# TOP.net
KiCad netlist of a schematic drawn in Altium Designer
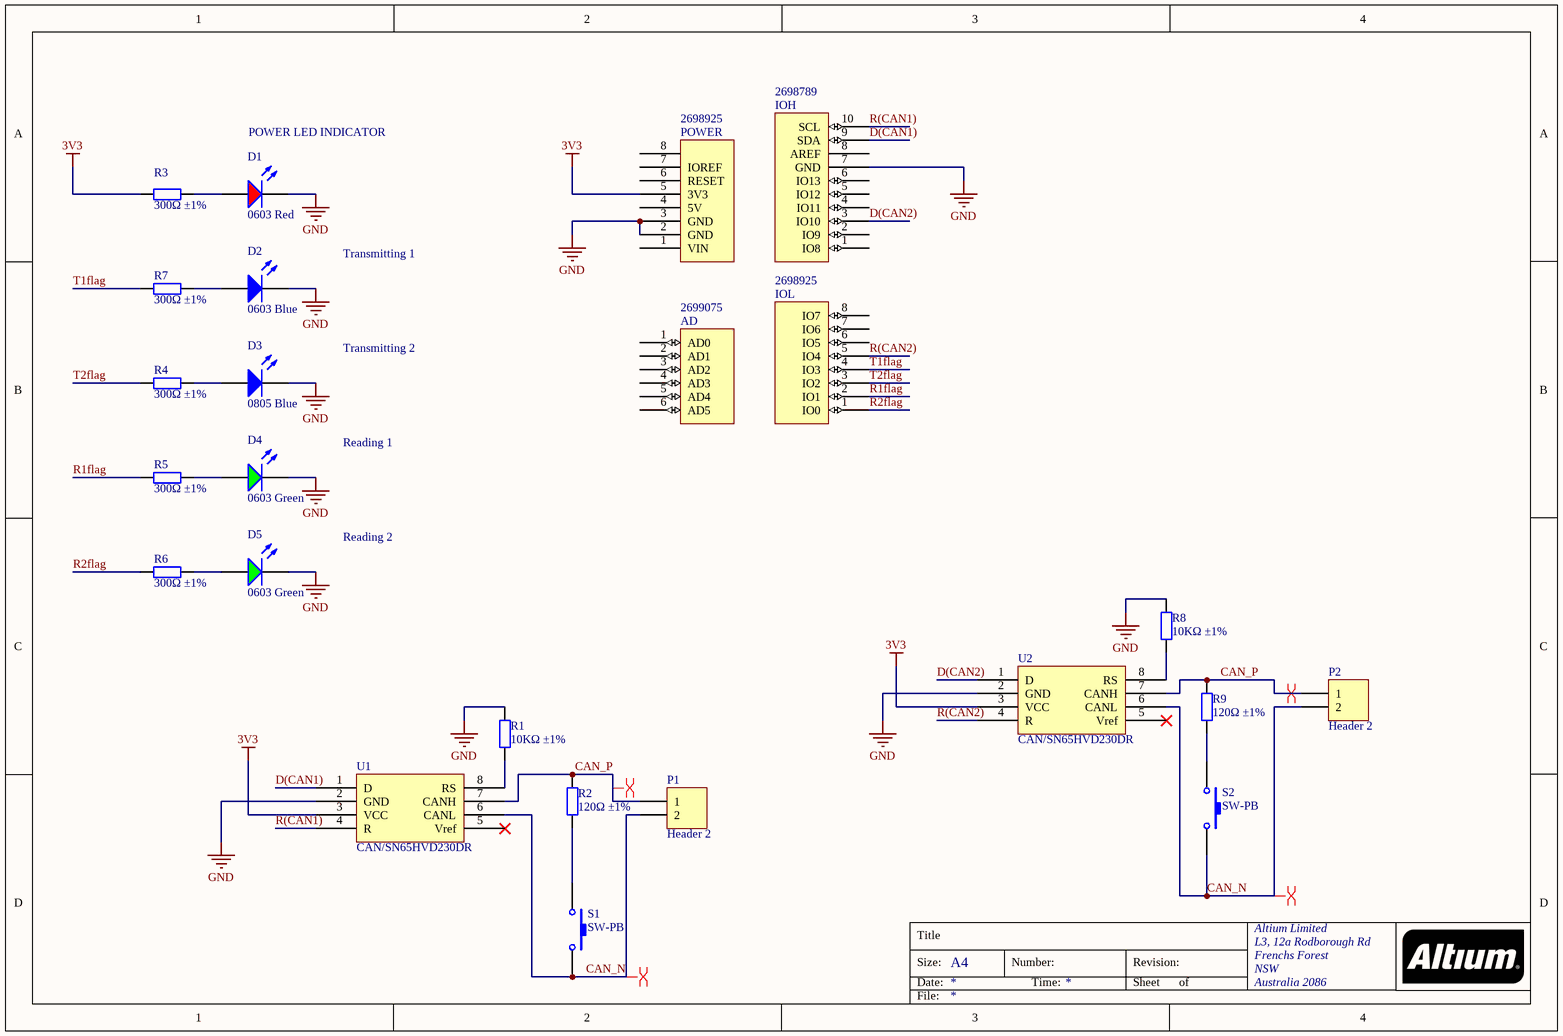
[diagram p0: TOP.SchDoc]

(export (version "E")
  (design (tool "Eeschema 10.0.6"))
  (components
    (comp (ref "AD")
      (value "AD")
      (footprint "Header:Header 6x1 8.5mm")
      (fields (field (name "SUPPLIER PART NUMBER 4") "2699075"))
      (libsource (lib "Header") (part "AD"))
    )
    (comp (ref "D1")
      (value "0603 Red")
      (footprint "0603_LED_S1")
      (description "LED")
      (libsource (lib "LED") (part "0603 LED Red"))
    )
    (comp (ref "D2")
      (value "0603 Blue")
      (footprint "0603_LED_S1")
      (description "LED")
      (libsource (lib "LED") (part "0603 LED Blue"))
    )
    (comp (ref "D3")
      (value "0805 Blue")
      (footprint "0805_LED_S1")
      (description "LED")
      (libsource (lib "LED") (part "0805 LED Blue"))
    )
    (comp (ref "D4")
      (value "0603 Green")
      (footprint "0603_LED_S1")
      (description "LED")
      (libsource (lib "LED") (part "0603 LED Green"))
    )
    (comp (ref "D5")
      (value "0603 Green")
      (footprint "0603_LED_S1")
      (description "LED")
      (libsource (lib "LED") (part "0603 LED Green"))
    )
    (comp (ref "IOH")
      (value "IOH")
      (footprint "Header:Header 10x1 8.5mm")
      (fields (field (name "SUPPLIER PART NUMBER 3") "2698789"))
      (libsource (lib "Header") (part "IOH"))
    )
    (comp (ref "IOL")
      (value "IOL")
      (footprint "Header 8x1 8.5mm")
      (fields (field (name "SUPPLIER PART NUMBER 4") "2698925"))
      (libsource (lib "Header") (part "IOL"))
    )
    (comp (ref "P1")
      (value "Header 2")
      (footprint "HDR1X2")
      (description "Header, 2-Pin")
      (fields (field (name "PUBLISHER") "Altium Limited"))
      (libsource (lib "Miscellaneous Connectors") (part "Header 2"))
    )
    (comp (ref "P2")
      (value "Header 2")
      (footprint "HDR1X2")
      (description "Header, 2-Pin")
      (fields (field (name "PUBLISHER") "Altium Limited"))
      (libsource (lib "Miscellaneous Connectors") (part "Header 2"))
    )
    (comp (ref "POWER")
      (value "POWER_UNO")
      (footprint "Header 8x1 8.5mm")
      (fields (field (name "SUPPLIER PART NUMBER 4") "2698925"))
      (libsource (lib "Header") (part "POWER_UNO"))
    )
    (comp (ref "R1")
      (value "10KΩ ±1%")
      (footprint "0603_R")
      (description "Chip resistor")
      (fields (field (name "MANUFACTURER") "Uniroyal Elec") (field (name "PARTNUMBER") "0603WAF1002T5E"))
      (libsource (lib "RES") (part "0603 10K (1002) 1%"))
    )
    (comp (ref "R2")
      (value "120Ω ±1%")
      (footprint "0603_R")
      (description "Chip resistor")
      (fields (field (name "MANUFACTURER") "Uniroyal Elec") (field (name "PARTNUMBER") "0603WAF1200T5E"))
      (libsource (lib "RES") (part "0603 120R (1200) 1%"))
    )
    (comp (ref "R3")
      (value "300Ω ±1%")
      (footprint "0603_R")
      (description "Chip resistor")
      (fields (field (name "MANUFACTURER") "Uniroyal Elec") (field (name "PARTNUMBER") "0603WAF3000T5E"))
      (libsource (lib "RES") (part "0603 300R (3000) 1%"))
    )
    (comp (ref "R4")
      (value "300Ω ±1%")
      (footprint "0603_R")
      (description "Chip resistor")
      (fields (field (name "MANUFACTURER") "Uniroyal Elec") (field (name "PARTNUMBER") "0603WAF3000T5E"))
      (libsource (lib "RES") (part "0603 300R (3000) 1%"))
    )
    (comp (ref "R5")
      (value "300Ω ±1%")
      (footprint "0603_R")
      (description "Chip resistor")
      (fields (field (name "MANUFACTURER") "Uniroyal Elec") (field (name "PARTNUMBER") "0603WAF3000T5E"))
      (libsource (lib "RES") (part "0603 300R (3000) 1%"))
    )
    (comp (ref "R6")
      (value "300Ω ±1%")
      (footprint "0603_R")
      (description "Chip resistor")
      (fields (field (name "MANUFACTURER") "Uniroyal Elec") (field (name "PARTNUMBER") "0603WAF3000T5E"))
      (libsource (lib "RES") (part "0603 300R (3000) 1%"))
    )
    (comp (ref "R7")
      (value "300Ω ±1%")
      (footprint "0603_R")
      (description "Chip resistor")
      (fields (field (name "MANUFACTURER") "Uniroyal Elec") (field (name "PARTNUMBER") "0603WAF3000T5E"))
      (libsource (lib "RES") (part "0603 300R (3000) 1%"))
    )
    (comp (ref "R8")
      (value "10KΩ ±1%")
      (footprint "0603_R")
      (description "Chip resistor")
      (fields (field (name "MANUFACTURER") "Uniroyal Elec") (field (name "PARTNUMBER") "0603WAF1002T5E"))
      (libsource (lib "RES") (part "0603 10K (1002) 1%"))
    )
    (comp (ref "R9")
      (value "120Ω ±1%")
      (footprint "0603_R")
      (description "Chip resistor")
      (fields (field (name "MANUFACTURER") "Uniroyal Elec") (field (name "PARTNUMBER") "0603WAF1200T5E"))
      (libsource (lib "RES") (part "0603 120R (1200) 1%"))
    )
    (comp (ref "S1")
      (value "SW-PB")
      (footprint "SPST-2")
      (description "Switch")
      (fields (field (name "PUBLISHER") "Altium Limited"))
      (libsource (lib "Miscellaneous Devices") (part "SW-PB"))
    )
    (comp (ref "S2")
      (value "SW-PB")
      (footprint "SPST-2")
      (description "Switch")
      (fields (field (name "PUBLISHER") "Altium Limited"))
      (libsource (lib "Miscellaneous Devices") (part "SW-PB"))
    )
    (comp (ref "U1")
      (value "CAN/SN65HVD230DR")
      (footprint "SOIC-8_150mil")
      (description "CAN")
      (libsource (lib "IC") (part "CAN/SN65HVD230DR_[C12084]"))
    )
    (comp (ref "U2")
      (value "CAN/SN65HVD230DR")
      (footprint "SOIC-8_150mil")
      (description "CAN")
      (libsource (lib "IC") (part "CAN/SN65HVD230DR_[C12084]"))
    )
  )
  (nets
    (net (code "1") (name "/CAN_N") (class "Default")
      (node (ref "P1") (pin "2") (pinfunction "2_2") (pintype "passive"))
      (node (ref "P2") (pin "2") (pinfunction "2_2") (pintype "passive"))
      (node (ref "S1") (pin "2") (pinfunction "2_2") (pintype "passive"))
      (node (ref "S2") (pin "2") (pinfunction "2_2") (pintype "passive"))
      (node (ref "U1") (pin "6") (pinfunction "CANL_6") (pintype "passive"))
      (node (ref "U2") (pin "6") (pinfunction "CANL_6") (pintype "passive"))
    )
    (net (code "2") (name "/CAN_P") (class "Default")
      (node (ref "P1") (pin "1") (pinfunction "1_1") (pintype "passive"))
      (node (ref "P2") (pin "1") (pinfunction "1_1") (pintype "passive"))
      (node (ref "R2") (pin "2") (pinfunction "2_2") (pintype "passive"))
      (node (ref "R9") (pin "2") (pinfunction "2_2") (pintype "passive"))
      (node (ref "U1") (pin "7") (pinfunction "CANH_7") (pintype "passive"))
      (node (ref "U2") (pin "7") (pinfunction "CANH_7") (pintype "passive"))
    )
    (net (code "3") (name "/D(CAN1)") (class "Default")
      (node (ref "IOH") (pin "9") (pinfunction "SDA_9") (pintype "bidirectional"))
      (node (ref "U1") (pin "1") (pinfunction "D_1") (pintype "passive"))
    )
    (net (code "4") (name "/D(CAN2)") (class "Default")
      (node (ref "IOH") (pin "3") (pinfunction "IO10_3") (pintype "bidirectional"))
      (node (ref "U2") (pin "1") (pinfunction "D_1") (pintype "passive"))
    )
    (net (code "5") (name "/R(CAN1)") (class "Default")
      (node (ref "IOH") (pin "10") (pinfunction "SCL_10") (pintype "bidirectional"))
      (node (ref "U1") (pin "4") (pinfunction "R_4") (pintype "passive"))
    )
    (net (code "6") (name "/R(CAN2)") (class "Default")
      (node (ref "IOL") (pin "5") (pinfunction "IO4_5") (pintype "bidirectional"))
      (node (ref "U2") (pin "4") (pinfunction "R_4") (pintype "passive"))
    )
    (net (code "7") (name "/R1flag") (class "Default")
      (node (ref "IOL") (pin "2") (pinfunction "IO1_2") (pintype "bidirectional"))
      (node (ref "R5") (pin "1") (pinfunction "1_1") (pintype "passive"))
    )
    (net (code "8") (name "/R2flag") (class "Default")
      (node (ref "IOL") (pin "1") (pinfunction "IO0_1") (pintype "bidirectional"))
      (node (ref "R6") (pin "1") (pinfunction "1_1") (pintype "passive"))
    )
    (net (code "9") (name "/T1flag") (class "Default")
      (node (ref "IOL") (pin "4") (pinfunction "IO3_4") (pintype "bidirectional"))
      (node (ref "R7") (pin "1") (pinfunction "1_1") (pintype "passive"))
    )
    (net (code "10") (name "/T2flag") (class "Default")
      (node (ref "IOL") (pin "3") (pinfunction "IO2_3") (pintype "bidirectional"))
      (node (ref "R4") (pin "1") (pinfunction "1_1") (pintype "passive"))
    )
    (net (code "11") (name "3V3") (class "Default")
      (node (ref "POWER") (pin "5") (pinfunction "3V3_5") (pintype "power_in"))
      (node (ref "R3") (pin "1") (pinfunction "1_1") (pintype "passive"))
      (node (ref "U1") (pin "3") (pinfunction "VCC_3") (pintype "passive"))
      (node (ref "U2") (pin "3") (pinfunction "VCC_3") (pintype "passive"))
    )
    (net (code "12") (name "GND") (class "Default")
      (node (ref "D1") (pin "K") (pinfunction "K_K") (pintype "passive"))
      (node (ref "D2") (pin "K") (pinfunction "K_K") (pintype "passive"))
      (node (ref "D3") (pin "K") (pinfunction "K_K") (pintype "passive"))
      (node (ref "D4") (pin "K") (pinfunction "K_K") (pintype "passive"))
      (node (ref "D5") (pin "K") (pinfunction "K_K") (pintype "passive"))
      (node (ref "IOH") (pin "7") (pinfunction "GND_7") (pintype "power_in"))
      (node (ref "POWER") (pin "2") (pinfunction "GND_2") (pintype "power_in"))
      (node (ref "POWER") (pin "3") (pinfunction "GND_3") (pintype "power_in"))
      (node (ref "R1") (pin "2") (pinfunction "2_2") (pintype "passive"))
      (node (ref "R8") (pin "2") (pinfunction "2_2") (pintype "passive"))
      (node (ref "U1") (pin "2") (pinfunction "GND_2") (pintype "passive"))
      (node (ref "U2") (pin "2") (pinfunction "GND_2") (pintype "passive"))
    )
    (net (code "13") (name "Net-(D1-PadA)") (class "Default")
      (node (ref "D1") (pin "A") (pinfunction "A_A") (pintype "passive"))
      (node (ref "R3") (pin "2") (pinfunction "2_2") (pintype "passive"))
    )
    (net (code "14") (name "Net-(D2-PadA)") (class "Default")
      (node (ref "D2") (pin "A") (pinfunction "A_A") (pintype "passive"))
      (node (ref "R7") (pin "2") (pinfunction "2_2") (pintype "passive"))
    )
    (net (code "15") (name "Net-(D3-PadA)") (class "Default")
      (node (ref "D3") (pin "A") (pinfunction "A_A") (pintype "passive"))
      (node (ref "R4") (pin "2") (pinfunction "2_2") (pintype "passive"))
    )
    (net (code "16") (name "Net-(D4-PadA)") (class "Default")
      (node (ref "D4") (pin "A") (pinfunction "A_A") (pintype "passive"))
      (node (ref "R5") (pin "2") (pinfunction "2_2") (pintype "passive"))
    )
    (net (code "17") (name "Net-(D5-PadA)") (class "Default")
      (node (ref "D5") (pin "A") (pinfunction "A_A") (pintype "passive"))
      (node (ref "R6") (pin "2") (pinfunction "2_2") (pintype "passive"))
    )
    (net (code "18") (name "Net-(R2-Pad1)") (class "Default")
      (node (ref "R2") (pin "1") (pinfunction "1_1") (pintype "passive"))
      (node (ref "S1") (pin "1") (pinfunction "1_1") (pintype "passive"))
    )
    (net (code "19") (name "Net-(R9-Pad1)") (class "Default")
      (node (ref "R9") (pin "1") (pinfunction "1_1") (pintype "passive"))
      (node (ref "S2") (pin "1") (pinfunction "1_1") (pintype "passive"))
    )
    (net (code "20") (name "Net-(U1-RS)") (class "Default")
      (node (ref "R1") (pin "1") (pinfunction "1_1") (pintype "passive"))
      (node (ref "U1") (pin "8") (pinfunction "RS_8") (pintype "passive"))
    )
    (net (code "21") (name "Net-(U2-RS)") (class "Default")
      (node (ref "R8") (pin "1") (pinfunction "1_1") (pintype "passive"))
      (node (ref "U2") (pin "8") (pinfunction "RS_8") (pintype "passive"))
    )
    (net (code "22") (name "unconnected-(AD-AD0-Pad1)") (class "Default")
      (node (ref "AD") (pin "1") (pinfunction "AD0_1") (pintype "bidirectional"))
    )
    (net (code "23") (name "unconnected-(AD-AD1-Pad2)") (class "Default")
      (node (ref "AD") (pin "2") (pinfunction "AD1_2") (pintype "bidirectional"))
    )
    (net (code "24") (name "unconnected-(AD-AD2-Pad3)") (class "Default")
      (node (ref "AD") (pin "3") (pinfunction "AD2_3") (pintype "bidirectional"))
    )
    (net (code "25") (name "unconnected-(AD-AD3-Pad4)") (class "Default")
      (node (ref "AD") (pin "4") (pinfunction "AD3_4") (pintype "bidirectional"))
    )
    (net (code "26") (name "unconnected-(AD-AD4-Pad5)") (class "Default")
      (node (ref "AD") (pin "5") (pinfunction "AD4_5") (pintype "bidirectional"))
    )
    (net (code "27") (name "unconnected-(AD-AD5-Pad6)") (class "Default")
      (node (ref "AD") (pin "6") (pinfunction "AD5_6") (pintype "bidirectional"))
    )
    (net (code "28") (name "unconnected-(IOH-AREF-Pad8)") (class "Default")
      (node (ref "IOH") (pin "8") (pinfunction "AREF_8") (pintype "passive"))
    )
    (net (code "29") (name "unconnected-(IOH-IO8-Pad1)") (class "Default")
      (node (ref "IOH") (pin "1") (pinfunction "IO8_1") (pintype "bidirectional"))
    )
    (net (code "30") (name "unconnected-(IOH-IO9-Pad2)") (class "Default")
      (node (ref "IOH") (pin "2") (pinfunction "IO9_2") (pintype "bidirectional"))
    )
    (net (code "31") (name "unconnected-(IOH-IO11-Pad4)") (class "Default")
      (node (ref "IOH") (pin "4") (pinfunction "IO11_4") (pintype "bidirectional"))
    )
    (net (code "32") (name "unconnected-(IOH-IO12-Pad5)") (class "Default")
      (node (ref "IOH") (pin "5") (pinfunction "IO12_5") (pintype "bidirectional"))
    )
    (net (code "33") (name "unconnected-(IOH-IO13-Pad6)") (class "Default")
      (node (ref "IOH") (pin "6") (pinfunction "IO13_6") (pintype "bidirectional"))
    )
    (net (code "34") (name "unconnected-(IOL-IO5-Pad6)") (class "Default")
      (node (ref "IOL") (pin "6") (pinfunction "IO5_6") (pintype "bidirectional"))
    )
    (net (code "35") (name "unconnected-(IOL-IO6-Pad7)") (class "Default")
      (node (ref "IOL") (pin "7") (pinfunction "IO6_7") (pintype "bidirectional"))
    )
    (net (code "36") (name "unconnected-(IOL-IO7-Pad8)") (class "Default")
      (node (ref "IOL") (pin "8") (pinfunction "IO7_8") (pintype "bidirectional"))
    )
    (net (code "37") (name "unconnected-(POWER-5V-Pad4)") (class "Default")
      (node (ref "POWER") (pin "4") (pinfunction "5V_4") (pintype "power_in"))
    )
    (net (code "38") (name "unconnected-(POWER-IOREF-Pad7)") (class "Default")
      (node (ref "POWER") (pin "7") (pinfunction "IOREF_7") (pintype "power_in"))
    )
    (net (code "39") (name "unconnected-(POWER-Pad8)") (class "Default")
      (node (ref "POWER") (pin "8") (pintype "passive"))
    )
    (net (code "40") (name "unconnected-(POWER-RESET-Pad6)") (class "Default")
      (node (ref "POWER") (pin "6") (pinfunction "RESET_6") (pintype "passive"))
    )
    (net (code "41") (name "unconnected-(POWER-VIN-Pad1)") (class "Default")
      (node (ref "POWER") (pin "1") (pinfunction "VIN_1") (pintype "power_in"))
    )
    (net (code "42") (name "unconnected-(U1-Vref-Pad5)") (class "Default")
      (node (ref "U1") (pin "5") (pinfunction "Vref_5") (pintype "passive+no_connect"))
    )
    (net (code "43") (name "unconnected-(U2-Vref-Pad5)") (class "Default")
      (node (ref "U2") (pin "5") (pinfunction "Vref_5") (pintype "passive+no_connect"))
    )
  )
)
